# Board1.net
KiCad netlist of a schematic drawn in EAGLE
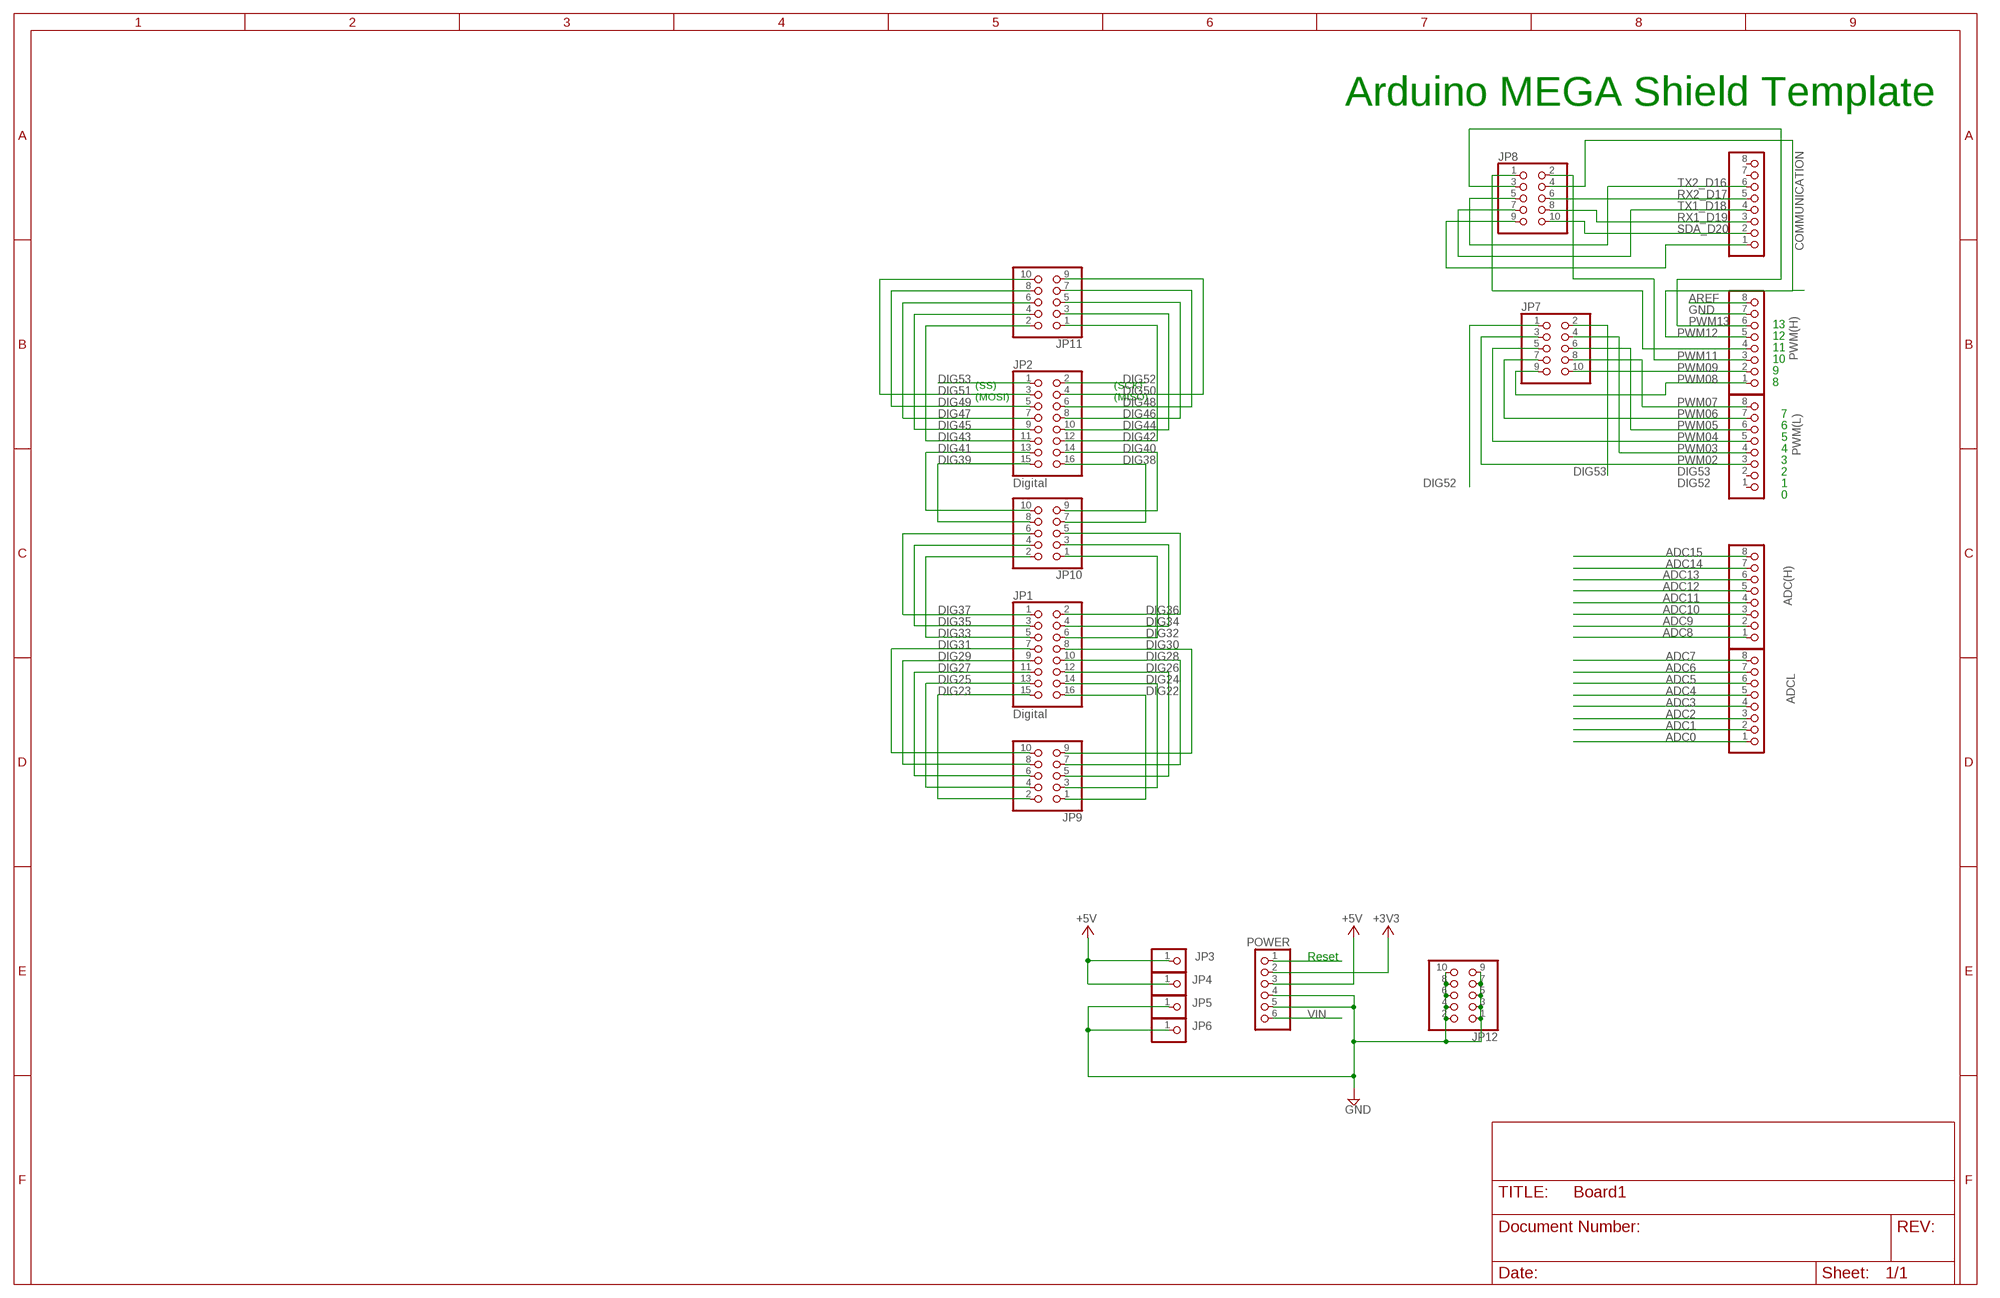
[diagram p0: schematic, sheet 1]

(export (version "E")
  (design (tool "Eeschema 10.0.6"))
  (components
    (comp (ref "ADC(H)")
      (value "PINHD-1X8")
      (footprint "eagle-import:1X08")
      (libsource (lib "eagle-import") (part "PINHD-1X8"))
    )
    (comp (ref "ADCL")
      (value "PINHD-1X8")
      (footprint "eagle-import:1X08")
      (libsource (lib "eagle-import") (part "PINHD-1X8"))
    )
    (comp (ref "COMMUNICATION")
      (value "PINHD-1X8")
      (footprint "eagle-import:1X08")
      (libsource (lib "eagle-import") (part "PINHD-1X8"))
    )
    (comp (ref "JP1")
      (value "Digital")
      (footprint "eagle-import:2X08")
      (libsource (lib "eagle-import") (part "PINHD-2X8"))
    )
    (comp (ref "JP2")
      (value "Digital")
      (footprint "eagle-import:2X08")
      (libsource (lib "eagle-import") (part "PINHD-2X8"))
    )
    (comp (ref "JP3")
      (value "PINHD-1X1")
      (footprint "eagle-import:1X01")
      (libsource (lib "eagle-import") (part "PINHD-1X1"))
    )
    (comp (ref "JP4")
      (value "PINHD-1X1")
      (footprint "eagle-import:1X01")
      (libsource (lib "eagle-import") (part "PINHD-1X1"))
    )
    (comp (ref "JP5")
      (value "PINHD-1X1")
      (footprint "eagle-import:1X01")
      (libsource (lib "eagle-import") (part "PINHD-1X1"))
    )
    (comp (ref "JP6")
      (value "PINHD-1X1")
      (footprint "eagle-import:1X01")
      (libsource (lib "eagle-import") (part "PINHD-1X1"))
    )
    (comp (ref "JP7")
      (value "PINHD-2X5SMT")
      (footprint "eagle-import:2X05_SMT")
      (libsource (lib "eagle-import") (part "PINHD-2X5SMT"))
    )
    (comp (ref "JP8")
      (value "PINHD-2X5SMT")
      (footprint "eagle-import:2X05_SMT")
      (libsource (lib "eagle-import") (part "PINHD-2X5SMT"))
    )
    (comp (ref "JP9")
      (value "PINHD-2X5SMT")
      (footprint "eagle-import:2X05_SMT")
      (libsource (lib "eagle-import") (part "PINHD-2X5SMT"))
    )
    (comp (ref "JP10")
      (value "PINHD-2X5SMT")
      (footprint "eagle-import:2X05_SMT")
      (libsource (lib "eagle-import") (part "PINHD-2X5SMT"))
    )
    (comp (ref "JP11")
      (value "PINHD-2X5SMT")
      (footprint "eagle-import:2X05_SMT")
      (libsource (lib "eagle-import") (part "PINHD-2X5SMT"))
    )
    (comp (ref "JP12")
      (value "PINHD-2X5SMT")
      (footprint "eagle-import:2X05_SMT")
      (libsource (lib "eagle-import") (part "PINHD-2X5SMT"))
    )
    (comp (ref "POWER")
      (value "PINHD-1X6")
      (footprint "eagle-import:1X06")
      (libsource (lib "eagle-import") (part "PINHD-1X6"))
    )
    (comp (ref "PWM(H)")
      (value "PINHD-1X8")
      (footprint "eagle-import:1X08")
      (libsource (lib "eagle-import") (part "PINHD-1X8"))
    )
    (comp (ref "PWM(L)")
      (value "PINHD-1X8")
      (footprint "eagle-import:1X08")
      (libsource (lib "eagle-import") (part "PINHD-1X8"))
    )
  )
  (nets
    (net (code "1") (name "+3V3") (class "Default")
      (node (ref "POWER") (pin "2") (pinfunction "2_2") (pintype "passive"))
    )
    (net (code "2") (name "+5V") (class "Default")
      (node (ref "JP3") (pin "1") (pinfunction "1_1") (pintype "passive"))
      (node (ref "JP4") (pin "1") (pinfunction "1_1") (pintype "passive"))
      (node (ref "POWER") (pin "3") (pinfunction "3_3") (pintype "passive"))
    )
    (net (code "3") (name "/ADC0") (class "Default")
      (node (ref "ADCL") (pin "1") (pinfunction "1_1") (pintype "passive"))
    )
    (net (code "4") (name "/ADC1") (class "Default")
      (node (ref "ADCL") (pin "2") (pinfunction "2_2") (pintype "passive"))
    )
    (net (code "5") (name "/ADC2") (class "Default")
      (node (ref "ADCL") (pin "3") (pinfunction "3_3") (pintype "passive"))
    )
    (net (code "6") (name "/ADC3") (class "Default")
      (node (ref "ADCL") (pin "4") (pinfunction "4_4") (pintype "passive"))
    )
    (net (code "7") (name "/ADC4") (class "Default")
      (node (ref "ADCL") (pin "5") (pinfunction "5_5") (pintype "passive"))
    )
    (net (code "8") (name "/ADC5") (class "Default")
      (node (ref "ADCL") (pin "6") (pinfunction "6_6") (pintype "passive"))
    )
    (net (code "9") (name "/ADC6") (class "Default")
      (node (ref "ADCL") (pin "7") (pinfunction "7_7") (pintype "passive"))
    )
    (net (code "10") (name "/ADC7") (class "Default")
      (node (ref "ADCL") (pin "8") (pinfunction "8_8") (pintype "passive"))
    )
    (net (code "11") (name "/ADC8") (class "Default")
      (node (ref "ADC(H)") (pin "1") (pinfunction "1_1") (pintype "passive"))
    )
    (net (code "12") (name "/ADC9") (class "Default")
      (node (ref "ADC(H)") (pin "2") (pinfunction "2_2") (pintype "passive"))
    )
    (net (code "13") (name "/ADC10") (class "Default")
      (node (ref "ADC(H)") (pin "3") (pinfunction "3_3") (pintype "passive"))
    )
    (net (code "14") (name "/ADC11") (class "Default")
      (node (ref "ADC(H)") (pin "4") (pinfunction "4_4") (pintype "passive"))
    )
    (net (code "15") (name "/ADC12") (class "Default")
      (node (ref "ADC(H)") (pin "5") (pinfunction "5_5") (pintype "passive"))
    )
    (net (code "16") (name "/ADC13") (class "Default")
      (node (ref "ADC(H)") (pin "6") (pinfunction "6_6") (pintype "passive"))
    )
    (net (code "17") (name "/ADC14") (class "Default")
      (node (ref "ADC(H)") (pin "7") (pinfunction "7_7") (pintype "passive"))
    )
    (net (code "18") (name "/ADC15") (class "Default")
      (node (ref "ADC(H)") (pin "8") (pinfunction "8_8") (pintype "passive"))
    )
    (net (code "19") (name "/AREF") (class "Default")
      (node (ref "PWM(H)") (pin "8") (pinfunction "8_8") (pintype "passive"))
    )
    (net (code "20") (name "/DIG22") (class "Default")
      (node (ref "JP1") (pin "16") (pinfunction "16_16") (pintype "passive"))
      (node (ref "JP9") (pin "1") (pinfunction "1_1") (pintype "passive"))
    )
    (net (code "21") (name "/DIG23") (class "Default")
      (node (ref "JP1") (pin "15") (pinfunction "15_15") (pintype "passive"))
      (node (ref "JP9") (pin "2") (pinfunction "2_2") (pintype "passive"))
    )
    (net (code "22") (name "/DIG24") (class "Default")
      (node (ref "JP1") (pin "14") (pinfunction "14_14") (pintype "passive"))
      (node (ref "JP9") (pin "3") (pinfunction "3_3") (pintype "passive"))
    )
    (net (code "23") (name "/DIG25") (class "Default")
      (node (ref "JP1") (pin "13") (pinfunction "13_13") (pintype "passive"))
      (node (ref "JP9") (pin "4") (pinfunction "4_4") (pintype "passive"))
    )
    (net (code "24") (name "/DIG26") (class "Default")
      (node (ref "JP1") (pin "12") (pinfunction "12_12") (pintype "passive"))
      (node (ref "JP9") (pin "5") (pinfunction "5_5") (pintype "passive"))
    )
    (net (code "25") (name "/DIG27") (class "Default")
      (node (ref "JP1") (pin "11") (pinfunction "11_11") (pintype "passive"))
      (node (ref "JP9") (pin "6") (pinfunction "6_6") (pintype "passive"))
    )
    (net (code "26") (name "/DIG28") (class "Default")
      (node (ref "JP1") (pin "10") (pinfunction "10_10") (pintype "passive"))
      (node (ref "JP9") (pin "7") (pinfunction "7_7") (pintype "passive"))
    )
    (net (code "27") (name "/DIG29") (class "Default")
      (node (ref "JP1") (pin "9") (pinfunction "9_9") (pintype "passive"))
      (node (ref "JP9") (pin "8") (pinfunction "8_8") (pintype "passive"))
    )
    (net (code "28") (name "/DIG30") (class "Default")
      (node (ref "JP1") (pin "8") (pinfunction "8_8") (pintype "passive"))
      (node (ref "JP9") (pin "9") (pinfunction "9_9") (pintype "passive"))
    )
    (net (code "29") (name "/DIG31") (class "Default")
      (node (ref "JP1") (pin "7") (pinfunction "7_7") (pintype "passive"))
      (node (ref "JP9") (pin "10") (pinfunction "10_10") (pintype "passive"))
    )
    (net (code "30") (name "/DIG32") (class "Default")
      (node (ref "JP1") (pin "6") (pinfunction "6_6") (pintype "passive"))
      (node (ref "JP10") (pin "1") (pinfunction "1_1") (pintype "passive"))
    )
    (net (code "31") (name "/DIG33") (class "Default")
      (node (ref "JP1") (pin "5") (pinfunction "5_5") (pintype "passive"))
      (node (ref "JP10") (pin "2") (pinfunction "2_2") (pintype "passive"))
    )
    (net (code "32") (name "/DIG34") (class "Default")
      (node (ref "JP1") (pin "4") (pinfunction "4_4") (pintype "passive"))
      (node (ref "JP10") (pin "3") (pinfunction "3_3") (pintype "passive"))
    )
    (net (code "33") (name "/DIG35") (class "Default")
      (node (ref "JP1") (pin "3") (pinfunction "3_3") (pintype "passive"))
      (node (ref "JP10") (pin "4") (pinfunction "4_4") (pintype "passive"))
    )
    (net (code "34") (name "/DIG36") (class "Default")
      (node (ref "JP1") (pin "2") (pinfunction "2_2") (pintype "passive"))
      (node (ref "JP10") (pin "5") (pinfunction "5_5") (pintype "passive"))
    )
    (net (code "35") (name "/DIG37") (class "Default")
      (node (ref "JP1") (pin "1") (pinfunction "1_1") (pintype "passive"))
      (node (ref "JP10") (pin "6") (pinfunction "6_6") (pintype "passive"))
    )
    (net (code "36") (name "/DIG38") (class "Default")
      (node (ref "JP10") (pin "7") (pinfunction "7_7") (pintype "passive"))
      (node (ref "JP2") (pin "16") (pinfunction "16_16") (pintype "passive"))
    )
    (net (code "37") (name "/DIG39") (class "Default")
      (node (ref "JP10") (pin "8") (pinfunction "8_8") (pintype "passive"))
      (node (ref "JP2") (pin "15") (pinfunction "15_15") (pintype "passive"))
    )
    (net (code "38") (name "/DIG40") (class "Default")
      (node (ref "JP10") (pin "9") (pinfunction "9_9") (pintype "passive"))
      (node (ref "JP2") (pin "14") (pinfunction "14_14") (pintype "passive"))
    )
    (net (code "39") (name "/DIG41") (class "Default")
      (node (ref "JP10") (pin "10") (pinfunction "10_10") (pintype "passive"))
      (node (ref "JP2") (pin "13") (pinfunction "13_13") (pintype "passive"))
    )
    (net (code "40") (name "/DIG42") (class "Default")
      (node (ref "JP11") (pin "1") (pinfunction "1_1") (pintype "passive"))
      (node (ref "JP2") (pin "12") (pinfunction "12_12") (pintype "passive"))
    )
    (net (code "41") (name "/DIG43") (class "Default")
      (node (ref "JP11") (pin "2") (pinfunction "2_2") (pintype "passive"))
      (node (ref "JP2") (pin "11") (pinfunction "11_11") (pintype "passive"))
    )
    (net (code "42") (name "/DIG44") (class "Default")
      (node (ref "JP11") (pin "3") (pinfunction "3_3") (pintype "passive"))
      (node (ref "JP2") (pin "10") (pinfunction "10_10") (pintype "passive"))
    )
    (net (code "43") (name "/DIG45") (class "Default")
      (node (ref "JP11") (pin "4") (pinfunction "4_4") (pintype "passive"))
      (node (ref "JP2") (pin "9") (pinfunction "9_9") (pintype "passive"))
    )
    (net (code "44") (name "/DIG46") (class "Default")
      (node (ref "JP11") (pin "5") (pinfunction "5_5") (pintype "passive"))
      (node (ref "JP2") (pin "8") (pinfunction "8_8") (pintype "passive"))
    )
    (net (code "45") (name "/DIG47") (class "Default")
      (node (ref "JP11") (pin "6") (pinfunction "6_6") (pintype "passive"))
      (node (ref "JP2") (pin "7") (pinfunction "7_7") (pintype "passive"))
    )
    (net (code "46") (name "/DIG48") (class "Default")
      (node (ref "JP11") (pin "7") (pinfunction "7_7") (pintype "passive"))
      (node (ref "JP2") (pin "6") (pinfunction "6_6") (pintype "passive"))
    )
    (net (code "47") (name "/DIG49") (class "Default")
      (node (ref "JP11") (pin "8") (pinfunction "8_8") (pintype "passive"))
      (node (ref "JP2") (pin "5") (pinfunction "5_5") (pintype "passive"))
    )
    (net (code "48") (name "/DIG50") (class "Default")
      (node (ref "JP11") (pin "9") (pinfunction "9_9") (pintype "passive"))
      (node (ref "JP2") (pin "4") (pinfunction "4_4") (pintype "passive"))
    )
    (net (code "49") (name "/DIG51") (class "Default")
      (node (ref "JP11") (pin "10") (pinfunction "10_10") (pintype "passive"))
      (node (ref "JP2") (pin "3") (pinfunction "3_3") (pintype "passive"))
    )
    (net (code "50") (name "/DIG52") (class "Default")
      (node (ref "JP2") (pin "2") (pinfunction "2_2") (pintype "passive"))
      (node (ref "JP7") (pin "1") (pinfunction "1_1") (pintype "passive"))
    )
    (net (code "51") (name "/DIG53") (class "Default")
      (node (ref "JP2") (pin "1") (pinfunction "1_1") (pintype "passive"))
      (node (ref "JP7") (pin "2") (pinfunction "2_2") (pintype "passive"))
    )
    (net (code "52") (name "/PWM02") (class "Default")
      (node (ref "JP7") (pin "3") (pinfunction "3_3") (pintype "passive"))
      (node (ref "PWM(L)") (pin "3") (pinfunction "3_3") (pintype "passive"))
    )
    (net (code "53") (name "/PWM03") (class "Default")
      (node (ref "JP7") (pin "4") (pinfunction "4_4") (pintype "passive"))
      (node (ref "PWM(L)") (pin "4") (pinfunction "4_4") (pintype "passive"))
    )
    (net (code "54") (name "/PWM04") (class "Default")
      (node (ref "JP7") (pin "5") (pinfunction "5_5") (pintype "passive"))
      (node (ref "PWM(L)") (pin "5") (pinfunction "5_5") (pintype "passive"))
    )
    (net (code "55") (name "/PWM05") (class "Default")
      (node (ref "JP7") (pin "6") (pinfunction "6_6") (pintype "passive"))
      (node (ref "PWM(L)") (pin "6") (pinfunction "6_6") (pintype "passive"))
    )
    (net (code "56") (name "/PWM06") (class "Default")
      (node (ref "JP7") (pin "7") (pinfunction "7_7") (pintype "passive"))
      (node (ref "PWM(L)") (pin "7") (pinfunction "7_7") (pintype "passive"))
    )
    (net (code "57") (name "/PWM07") (class "Default")
      (node (ref "JP7") (pin "8") (pinfunction "8_8") (pintype "passive"))
      (node (ref "PWM(L)") (pin "8") (pinfunction "8_8") (pintype "passive"))
    )
    (net (code "58") (name "/PWM08") (class "Default")
      (node (ref "JP7") (pin "9") (pinfunction "9_9") (pintype "passive"))
      (node (ref "PWM(H)") (pin "1") (pinfunction "1_1") (pintype "passive"))
    )
    (net (code "59") (name "/PWM09") (class "Default")
      (node (ref "JP7") (pin "10") (pinfunction "10_10") (pintype "passive"))
      (node (ref "PWM(H)") (pin "2") (pinfunction "2_2") (pintype "passive"))
    )
    (net (code "60") (name "/PWM11") (class "Default")
      (node (ref "JP8") (pin "2") (pinfunction "2_2") (pintype "passive"))
      (node (ref "PWM(H)") (pin "3") (pinfunction "3_3") (pintype "passive"))
    )
    (net (code "61") (name "/PWM12") (class "Default")
      (node (ref "JP8") (pin "4") (pinfunction "4_4") (pintype "passive"))
      (node (ref "PWM(H)") (pin "5") (pinfunction "5_5") (pintype "passive"))
    )
    (net (code "62") (name "/PWM13") (class "Default")
      (node (ref "JP8") (pin "3") (pinfunction "3_3") (pintype "passive"))
      (node (ref "PWM(H)") (pin "6") (pinfunction "6_6") (pintype "passive"))
    )
    (net (code "63") (name "/RX1_D19") (class "Default")
      (node (ref "COMMUNICATION") (pin "3") (pinfunction "3_3") (pintype "passive"))
      (node (ref "JP8") (pin "8") (pinfunction "8_8") (pintype "passive"))
    )
    (net (code "64") (name "/RX2_D17") (class "Default")
      (node (ref "COMMUNICATION") (pin "5") (pinfunction "5_5") (pintype "passive"))
      (node (ref "JP8") (pin "6") (pinfunction "6_6") (pintype "passive"))
    )
    (net (code "65") (name "/SDA_D20") (class "Default")
      (node (ref "COMMUNICATION") (pin "1") (pinfunction "1_1") (pintype "passive"))
      (node (ref "JP8") (pin "9") (pinfunction "9_9") (pintype "passive"))
    )
    (net (code "66") (name "/TX1_D18") (class "Default")
      (node (ref "COMMUNICATION") (pin "4") (pinfunction "4_4") (pintype "passive"))
      (node (ref "JP8") (pin "7") (pinfunction "7_7") (pintype "passive"))
    )
    (net (code "67") (name "/TX2_D16") (class "Default")
      (node (ref "COMMUNICATION") (pin "6") (pinfunction "6_6") (pintype "passive"))
      (node (ref "JP8") (pin "5") (pinfunction "5_5") (pintype "passive"))
    )
    (net (code "68") (name "/VIN") (class "Default")
      (node (ref "POWER") (pin "6") (pinfunction "6_6") (pintype "passive"))
    )
    (net (code "69") (name "GND") (class "Default")
      (node (ref "JP12") (pin "1") (pinfunction "1_1") (pintype "passive"))
      (node (ref "JP12") (pin "10") (pinfunction "10_10") (pintype "passive"))
      (node (ref "JP12") (pin "2") (pinfunction "2_2") (pintype "passive"))
      (node (ref "JP12") (pin "3") (pinfunction "3_3") (pintype "passive"))
      (node (ref "JP12") (pin "4") (pinfunction "4_4") (pintype "passive"))
      (node (ref "JP12") (pin "5") (pinfunction "5_5") (pintype "passive"))
      (node (ref "JP12") (pin "6") (pinfunction "6_6") (pintype "passive"))
      (node (ref "JP12") (pin "7") (pinfunction "7_7") (pintype "passive"))
      (node (ref "JP12") (pin "8") (pinfunction "8_8") (pintype "passive"))
      (node (ref "JP12") (pin "9") (pinfunction "9_9") (pintype "passive"))
      (node (ref "JP5") (pin "1") (pinfunction "1_1") (pintype "passive"))
      (node (ref "JP6") (pin "1") (pinfunction "1_1") (pintype "passive"))
      (node (ref "POWER") (pin "4") (pinfunction "4_4") (pintype "passive"))
      (node (ref "POWER") (pin "5") (pinfunction "5_5") (pintype "passive"))
      (node (ref "PWM(H)") (pin "7") (pinfunction "7_7") (pintype "passive"))
    )
    (net (code "70") (name "Net-(COMMUNICATION-Pad2)") (class "Default")
      (node (ref "COMMUNICATION") (pin "2") (pinfunction "2_2") (pintype "passive"))
      (node (ref "JP8") (pin "10") (pinfunction "10_10") (pintype "passive"))
    )
    (net (code "71") (name "Net-(JP8-Pad1)") (class "Default")
      (node (ref "JP8") (pin "1") (pinfunction "1_1") (pintype "passive"))
      (node (ref "PWM(H)") (pin "4") (pinfunction "4_4") (pintype "passive"))
    )
    (net (code "72") (name "unconnected-(COMMUNICATION-Pad7)") (class "Default")
      (node (ref "COMMUNICATION") (pin "7") (pinfunction "7_7") (pintype "passive"))
    )
    (net (code "73") (name "unconnected-(COMMUNICATION-Pad8)") (class "Default")
      (node (ref "COMMUNICATION") (pin "8") (pinfunction "8_8") (pintype "passive"))
    )
    (net (code "74") (name "unconnected-(POWER-Pad1)") (class "Default")
      (node (ref "POWER") (pin "1") (pinfunction "1_1") (pintype "passive"))
    )
    (net (code "75") (name "unconnected-(PWM(L)-Pad1)") (class "Default")
      (node (ref "PWM(L)") (pin "1") (pinfunction "1_1") (pintype "passive"))
    )
    (net (code "76") (name "unconnected-(PWM(L)-Pad2)") (class "Default")
      (node (ref "PWM(L)") (pin "2") (pinfunction "2_2") (pintype "passive"))
    )
  )
)
